# PowerBus.net
KiCad netlist of a schematic drawn in EAGLE
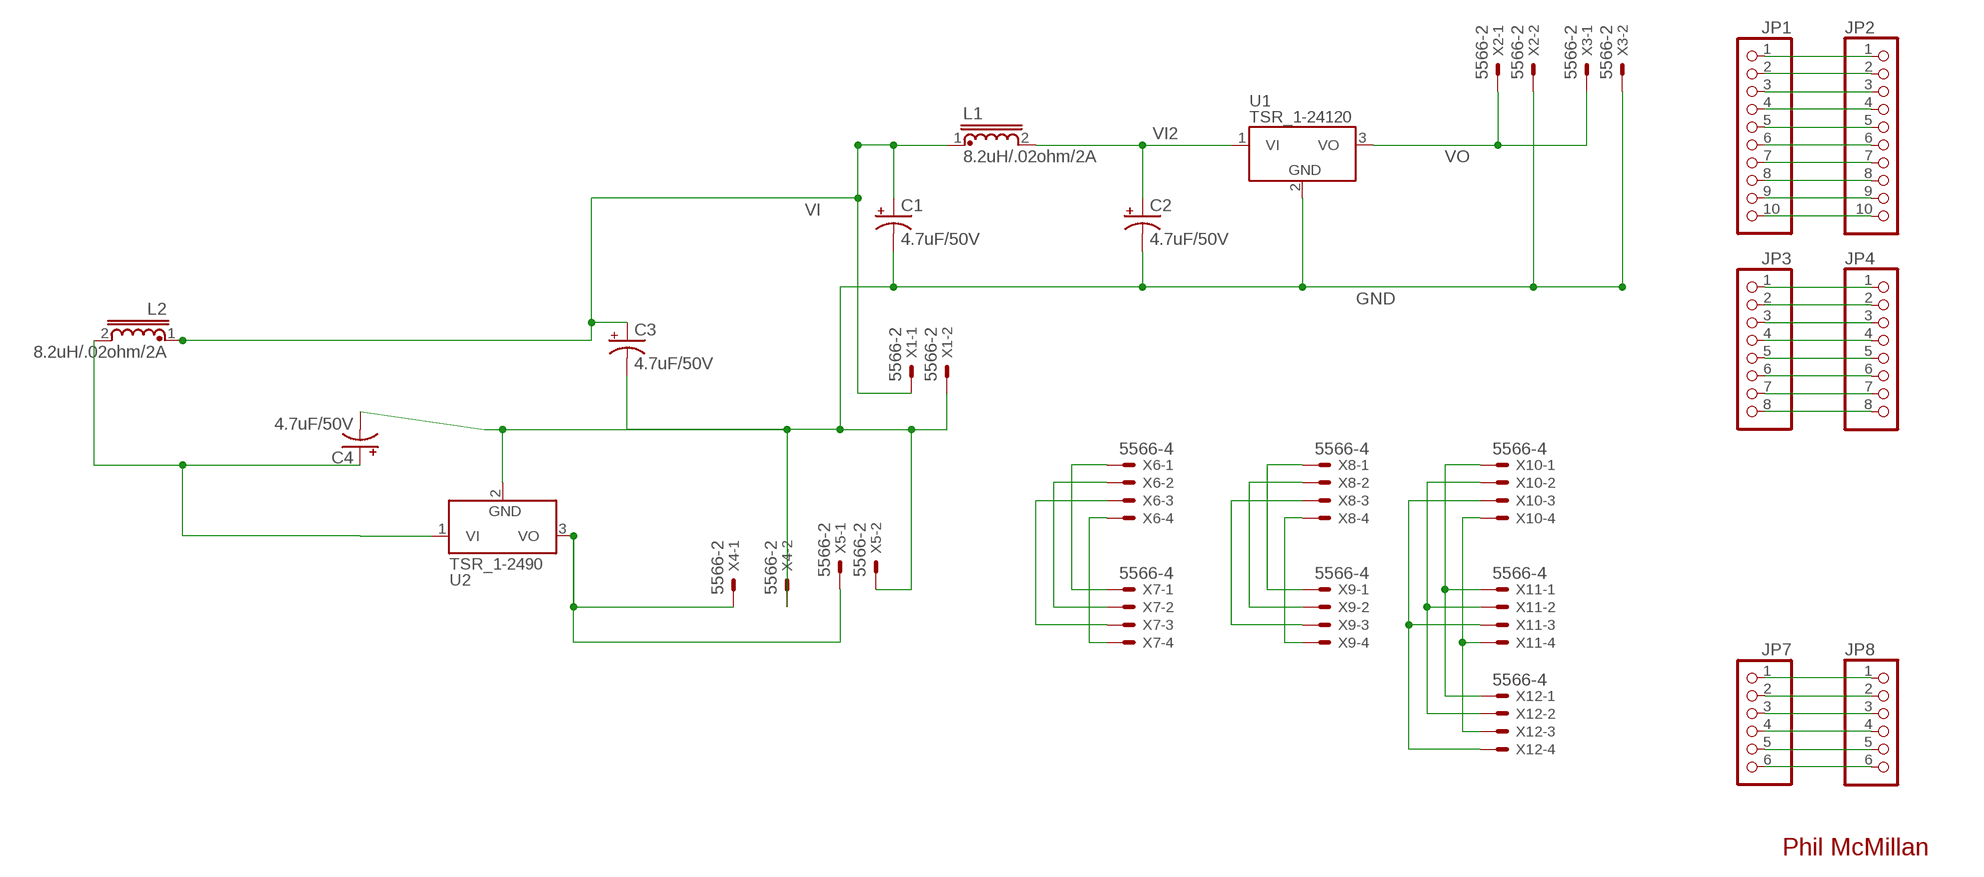
[diagram p0: schematic, sheet 1]

(export (version "E")
  (design (tool "Eeschema 10.0.6"))
  (components
    (comp (ref "C1")
      (value "4.7uF/50V")
      (footprint "eagle-import:E2-5")
      (libsource (lib "eagle-import") (part "CPOL-USE2-5"))
    )
    (comp (ref "C2")
      (value "4.7uF/50V")
      (footprint "eagle-import:E2-5")
      (libsource (lib "eagle-import") (part "CPOL-USE2-5"))
    )
    (comp (ref "C3")
      (value "4.7uF/50V")
      (footprint "eagle-import:E2-5")
      (libsource (lib "eagle-import") (part "CPOL-USE2-5"))
    )
    (comp (ref "C4")
      (value "4.7uF/50V")
      (footprint "eagle-import:E2-5")
      (libsource (lib "eagle-import") (part "CPOL-USE2-5"))
    )
    (comp (ref "JP1")
      (value "PINHD-1X10")
      (footprint "eagle-import:1X10")
      (libsource (lib "eagle-import") (part "PINHD-1X10"))
    )
    (comp (ref "JP2")
      (value "PINHD-1X10")
      (footprint "eagle-import:1X10")
      (libsource (lib "eagle-import") (part "PINHD-1X10"))
    )
    (comp (ref "JP3")
      (value "PINHD-1X8")
      (footprint "eagle-import:1X08")
      (libsource (lib "eagle-import") (part "PINHD-1X8"))
    )
    (comp (ref "JP4")
      (value "PINHD-1X8")
      (footprint "eagle-import:1X08")
      (libsource (lib "eagle-import") (part "PINHD-1X8"))
    )
    (comp (ref "JP7")
      (value "PINHD-1X6")
      (footprint "eagle-import:1X06")
      (libsource (lib "eagle-import") (part "PINHD-1X6"))
    )
    (comp (ref "JP8")
      (value "PINHD-1X6")
      (footprint "eagle-import:1X06")
      (libsource (lib "eagle-import") (part "PINHD-1X6"))
    )
    (comp (ref "L1")
      (value "8.2uH/.02ohm/2A")
      (footprint "eagle-import:MCAP103722016A-8R2MU")
      (libsource (lib "eagle-import") (part "MCAP103722016A-8R2MU"))
    )
    (comp (ref "L2")
      (value "8.2uH/.02ohm/2A")
      (footprint "eagle-import:MCAP103722016A-8R2MU")
      (libsource (lib "eagle-import") (part "MCAP103722016A-8R2MU"))
    )
    (comp (ref "U1")
      (value "TSR_1-24120")
      (footprint "eagle-import:TSR-1")
      (libsource (lib "eagle-import") (part "TSR_1-24120"))
    )
    (comp (ref "U2")
      (value "TSR_1-2490")
      (footprint "eagle-import:TSR-1")
      (libsource (lib "eagle-import") (part "TSR_1-2490"))
    )
    (comp (ref "X1")
      (value "5566-2")
      (footprint "eagle-import:5566-2")
      (libsource (lib "eagle-import") (part "5566-2"))
    )
    (comp (ref "X2")
      (value "5566-2")
      (footprint "eagle-import:5566-2")
      (libsource (lib "eagle-import") (part "5566-2"))
    )
    (comp (ref "X3")
      (value "5566-2")
      (footprint "eagle-import:5566-2")
      (libsource (lib "eagle-import") (part "5566-2"))
    )
    (comp (ref "X4")
      (value "5566-2")
      (footprint "eagle-import:5566-2")
      (libsource (lib "eagle-import") (part "5566-2"))
    )
    (comp (ref "X5")
      (value "5566-2")
      (footprint "eagle-import:5566-2")
      (libsource (lib "eagle-import") (part "5566-2"))
    )
    (comp (ref "X6")
      (value "5566-4")
      (footprint "eagle-import:5566-4")
      (libsource (lib "eagle-import") (part "5566-4"))
    )
    (comp (ref "X7")
      (value "5566-4")
      (footprint "eagle-import:5566-4")
      (libsource (lib "eagle-import") (part "5566-4"))
    )
    (comp (ref "X8")
      (value "5566-4")
      (footprint "eagle-import:5566-4")
      (libsource (lib "eagle-import") (part "5566-4"))
    )
    (comp (ref "X9")
      (value "5566-4")
      (footprint "eagle-import:5566-4")
      (libsource (lib "eagle-import") (part "5566-4"))
    )
    (comp (ref "X10")
      (value "5566-4")
      (footprint "eagle-import:5566-4")
      (libsource (lib "eagle-import") (part "5566-4"))
    )
    (comp (ref "X11")
      (value "5566-4")
      (footprint "eagle-import:5566-4")
      (libsource (lib "eagle-import") (part "5566-4"))
    )
    (comp (ref "X12")
      (value "5566-4")
      (footprint "eagle-import:5566-4")
      (libsource (lib "eagle-import") (part "5566-4"))
    )
  )
  (nets
    (net (code "1") (name "/GND") (class "Default")
      (node (ref "C1") (pin "-") (pinfunction "-_-") (pintype "passive"))
      (node (ref "C2") (pin "-") (pinfunction "-_-") (pintype "passive"))
      (node (ref "C3") (pin "-") (pinfunction "-_-") (pintype "passive"))
      (node (ref "C4") (pin "-") (pinfunction "-_-") (pintype "passive"))
      (node (ref "U1") (pin "2") (pinfunction "GND_2") (pintype "power_in"))
      (node (ref "U2") (pin "2") (pinfunction "GND_2") (pintype "power_in"))
      (node (ref "X1") (pin "2") (pinfunction "S_2") (pintype "passive"))
      (node (ref "X2") (pin "2") (pinfunction "S_2") (pintype "passive"))
      (node (ref "X3") (pin "2") (pinfunction "S_2") (pintype "passive"))
      (node (ref "X4") (pin "2") (pinfunction "S_2") (pintype "passive"))
      (node (ref "X5") (pin "2") (pinfunction "S_2") (pintype "passive"))
    )
    (net (code "2") (name "/VI") (class "Default")
      (node (ref "C1") (pin "+") (pinfunction "+_+") (pintype "passive"))
      (node (ref "C3") (pin "+") (pinfunction "+_+") (pintype "passive"))
      (node (ref "L1") (pin "1") (pinfunction "1_1") (pintype "passive"))
      (node (ref "L2") (pin "1") (pinfunction "1_1") (pintype "passive"))
      (node (ref "X1") (pin "1") (pinfunction "S_1") (pintype "passive"))
    )
    (net (code "3") (name "/VI2") (class "Default")
      (node (ref "C2") (pin "+") (pinfunction "+_+") (pintype "passive"))
      (node (ref "L1") (pin "2") (pinfunction "2_2") (pintype "passive"))
      (node (ref "U1") (pin "1") (pinfunction "VI_1") (pintype "power_in"))
    )
    (net (code "4") (name "/VO") (class "Default")
      (node (ref "U1") (pin "3") (pinfunction "VO_3") (pintype "power_in"))
      (node (ref "X2") (pin "1") (pinfunction "S_1") (pintype "passive"))
      (node (ref "X3") (pin "1") (pinfunction "S_1") (pintype "passive"))
    )
    (net (code "5") (name "Net-(JP1-Pad1)") (class "Default")
      (node (ref "JP1") (pin "1") (pinfunction "1_1") (pintype "passive"))
      (node (ref "JP2") (pin "1") (pinfunction "1_1") (pintype "passive"))
    )
    (net (code "6") (name "Net-(JP1-Pad2)") (class "Default")
      (node (ref "JP1") (pin "2") (pinfunction "2_2") (pintype "passive"))
      (node (ref "JP2") (pin "2") (pinfunction "2_2") (pintype "passive"))
    )
    (net (code "7") (name "Net-(JP1-Pad3)") (class "Default")
      (node (ref "JP1") (pin "3") (pinfunction "3_3") (pintype "passive"))
      (node (ref "JP2") (pin "3") (pinfunction "3_3") (pintype "passive"))
    )
    (net (code "8") (name "Net-(JP1-Pad4)") (class "Default")
      (node (ref "JP1") (pin "4") (pinfunction "4_4") (pintype "passive"))
      (node (ref "JP2") (pin "4") (pinfunction "4_4") (pintype "passive"))
    )
    (net (code "9") (name "Net-(JP1-Pad5)") (class "Default")
      (node (ref "JP1") (pin "5") (pinfunction "5_5") (pintype "passive"))
      (node (ref "JP2") (pin "5") (pinfunction "5_5") (pintype "passive"))
    )
    (net (code "10") (name "Net-(JP1-Pad6)") (class "Default")
      (node (ref "JP1") (pin "6") (pinfunction "6_6") (pintype "passive"))
      (node (ref "JP2") (pin "6") (pinfunction "6_6") (pintype "passive"))
    )
    (net (code "11") (name "Net-(JP1-Pad7)") (class "Default")
      (node (ref "JP1") (pin "7") (pinfunction "7_7") (pintype "passive"))
      (node (ref "JP2") (pin "7") (pinfunction "7_7") (pintype "passive"))
    )
    (net (code "12") (name "Net-(JP1-Pad8)") (class "Default")
      (node (ref "JP1") (pin "8") (pinfunction "8_8") (pintype "passive"))
      (node (ref "JP2") (pin "8") (pinfunction "8_8") (pintype "passive"))
    )
    (net (code "13") (name "Net-(JP1-Pad9)") (class "Default")
      (node (ref "JP1") (pin "9") (pinfunction "9_9") (pintype "passive"))
      (node (ref "JP2") (pin "9") (pinfunction "9_9") (pintype "passive"))
    )
    (net (code "14") (name "Net-(JP1-Pad10)") (class "Default")
      (node (ref "JP1") (pin "10") (pinfunction "10_10") (pintype "passive"))
      (node (ref "JP2") (pin "10") (pinfunction "10_10") (pintype "passive"))
    )
    (net (code "15") (name "Net-(JP3-Pad1)") (class "Default")
      (node (ref "JP3") (pin "1") (pinfunction "1_1") (pintype "passive"))
      (node (ref "JP4") (pin "1") (pinfunction "1_1") (pintype "passive"))
    )
    (net (code "16") (name "Net-(JP3-Pad2)") (class "Default")
      (node (ref "JP3") (pin "2") (pinfunction "2_2") (pintype "passive"))
      (node (ref "JP4") (pin "2") (pinfunction "2_2") (pintype "passive"))
    )
    (net (code "17") (name "Net-(JP3-Pad3)") (class "Default")
      (node (ref "JP3") (pin "3") (pinfunction "3_3") (pintype "passive"))
      (node (ref "JP4") (pin "3") (pinfunction "3_3") (pintype "passive"))
    )
    (net (code "18") (name "Net-(JP3-Pad4)") (class "Default")
      (node (ref "JP3") (pin "4") (pinfunction "4_4") (pintype "passive"))
      (node (ref "JP4") (pin "4") (pinfunction "4_4") (pintype "passive"))
    )
    (net (code "19") (name "Net-(JP3-Pad5)") (class "Default")
      (node (ref "JP3") (pin "5") (pinfunction "5_5") (pintype "passive"))
      (node (ref "JP4") (pin "5") (pinfunction "5_5") (pintype "passive"))
    )
    (net (code "20") (name "Net-(JP3-Pad6)") (class "Default")
      (node (ref "JP3") (pin "6") (pinfunction "6_6") (pintype "passive"))
      (node (ref "JP4") (pin "6") (pinfunction "6_6") (pintype "passive"))
    )
    (net (code "21") (name "Net-(JP3-Pad7)") (class "Default")
      (node (ref "JP3") (pin "7") (pinfunction "7_7") (pintype "passive"))
      (node (ref "JP4") (pin "7") (pinfunction "7_7") (pintype "passive"))
    )
    (net (code "22") (name "Net-(JP3-Pad8)") (class "Default")
      (node (ref "JP3") (pin "8") (pinfunction "8_8") (pintype "passive"))
      (node (ref "JP4") (pin "8") (pinfunction "8_8") (pintype "passive"))
    )
    (net (code "23") (name "Net-(JP7-Pad1)") (class "Default")
      (node (ref "JP7") (pin "1") (pinfunction "1_1") (pintype "passive"))
      (node (ref "JP8") (pin "1") (pinfunction "1_1") (pintype "passive"))
    )
    (net (code "24") (name "Net-(JP7-Pad2)") (class "Default")
      (node (ref "JP7") (pin "2") (pinfunction "2_2") (pintype "passive"))
      (node (ref "JP8") (pin "2") (pinfunction "2_2") (pintype "passive"))
    )
    (net (code "25") (name "Net-(JP7-Pad3)") (class "Default")
      (node (ref "JP7") (pin "3") (pinfunction "3_3") (pintype "passive"))
      (node (ref "JP8") (pin "3") (pinfunction "3_3") (pintype "passive"))
    )
    (net (code "26") (name "Net-(JP7-Pad4)") (class "Default")
      (node (ref "JP7") (pin "4") (pinfunction "4_4") (pintype "passive"))
      (node (ref "JP8") (pin "4") (pinfunction "4_4") (pintype "passive"))
    )
    (net (code "27") (name "Net-(JP7-Pad5)") (class "Default")
      (node (ref "JP7") (pin "5") (pinfunction "5_5") (pintype "passive"))
      (node (ref "JP8") (pin "5") (pinfunction "5_5") (pintype "passive"))
    )
    (net (code "28") (name "Net-(JP7-Pad6)") (class "Default")
      (node (ref "JP7") (pin "6") (pinfunction "6_6") (pintype "passive"))
      (node (ref "JP8") (pin "6") (pinfunction "6_6") (pintype "passive"))
    )
    (net (code "29") (name "Net-(U2-VI)") (class "Default")
      (node (ref "C4") (pin "+") (pinfunction "+_+") (pintype "passive"))
      (node (ref "L2") (pin "2") (pinfunction "2_2") (pintype "passive"))
      (node (ref "U2") (pin "1") (pinfunction "VI_1") (pintype "power_in"))
    )
    (net (code "30") (name "Net-(U2-VO)") (class "Default")
      (node (ref "U2") (pin "3") (pinfunction "VO_3") (pintype "power_in"))
      (node (ref "X4") (pin "1") (pinfunction "S_1") (pintype "passive"))
      (node (ref "X5") (pin "1") (pinfunction "S_1") (pintype "passive"))
    )
    (net (code "31") (name "Net-(X6A-S)") (class "Default")
      (node (ref "X6") (pin "1") (pinfunction "S_1") (pintype "passive"))
      (node (ref "X7") (pin "1") (pinfunction "S_1") (pintype "passive"))
    )
    (net (code "32") (name "Net-(X6B-S)") (class "Default")
      (node (ref "X6") (pin "2") (pinfunction "S_2") (pintype "passive"))
      (node (ref "X7") (pin "2") (pinfunction "S_2") (pintype "passive"))
    )
    (net (code "33") (name "Net-(X6C-S)") (class "Default")
      (node (ref "X6") (pin "3") (pinfunction "S_3") (pintype "passive"))
      (node (ref "X7") (pin "3") (pinfunction "S_3") (pintype "passive"))
    )
    (net (code "34") (name "Net-(X6D-S)") (class "Default")
      (node (ref "X6") (pin "4") (pinfunction "S_4") (pintype "passive"))
      (node (ref "X7") (pin "4") (pinfunction "S_4") (pintype "passive"))
    )
    (net (code "35") (name "Net-(X8A-S)") (class "Default")
      (node (ref "X8") (pin "1") (pinfunction "S_1") (pintype "passive"))
      (node (ref "X9") (pin "1") (pinfunction "S_1") (pintype "passive"))
    )
    (net (code "36") (name "Net-(X8B-S)") (class "Default")
      (node (ref "X8") (pin "2") (pinfunction "S_2") (pintype "passive"))
      (node (ref "X9") (pin "2") (pinfunction "S_2") (pintype "passive"))
    )
    (net (code "37") (name "Net-(X8C-S)") (class "Default")
      (node (ref "X8") (pin "3") (pinfunction "S_3") (pintype "passive"))
      (node (ref "X9") (pin "3") (pinfunction "S_3") (pintype "passive"))
    )
    (net (code "38") (name "Net-(X8D-S)") (class "Default")
      (node (ref "X8") (pin "4") (pinfunction "S_4") (pintype "passive"))
      (node (ref "X9") (pin "4") (pinfunction "S_4") (pintype "passive"))
    )
    (net (code "39") (name "Net-(X10A-S)") (class "Default")
      (node (ref "X10") (pin "1") (pinfunction "S_1") (pintype "passive"))
      (node (ref "X11") (pin "1") (pinfunction "S_1") (pintype "passive"))
      (node (ref "X12") (pin "1") (pinfunction "S_1") (pintype "passive"))
    )
    (net (code "40") (name "Net-(X10B-S)") (class "Default")
      (node (ref "X10") (pin "2") (pinfunction "S_2") (pintype "passive"))
      (node (ref "X11") (pin "2") (pinfunction "S_2") (pintype "passive"))
      (node (ref "X12") (pin "2") (pinfunction "S_2") (pintype "passive"))
    )
    (net (code "41") (name "Net-(X10C-S)") (class "Default")
      (node (ref "X10") (pin "3") (pinfunction "S_3") (pintype "passive"))
      (node (ref "X11") (pin "3") (pinfunction "S_3") (pintype "passive"))
      (node (ref "X12") (pin "4") (pinfunction "S_4") (pintype "passive"))
    )
    (net (code "42") (name "Net-(X10D-S)") (class "Default")
      (node (ref "X10") (pin "4") (pinfunction "S_4") (pintype "passive"))
      (node (ref "X11") (pin "4") (pinfunction "S_4") (pintype "passive"))
      (node (ref "X12") (pin "3") (pinfunction "S_3") (pintype "passive"))
    )
  )
)
